# single_valve_board.net
KiCad netlist of a schematic drawn in EAGLE
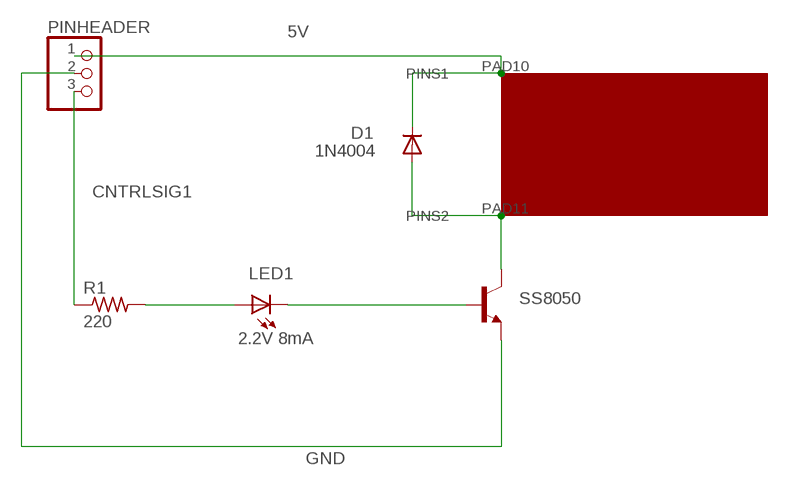
[diagram p0: schematic, sheet 1]

(export (version "E")
  (design (tool "Eeschema 10.0.6"))
  (components
    (comp (ref "D1")
      (value "1N4004")
      (footprint "eagle-import:DO41-10")
      (libsource (lib "eagle-import") (part "1N4004"))
    )
    (comp (ref "LED1")
      (value "2.2V 8mA")
      (footprint "eagle-import:LED5MM")
      (libsource (lib "eagle-import") (part "LED5MM"))
    )
    (comp (ref "PINHEADER")
      (value "PINHD-1X3")
      (footprint "eagle-import:1X03")
      (libsource (lib "eagle-import") (part "PINHD-1X3"))
    )
    (comp (ref "R1")
      (value "220")
      (footprint "eagle-import:0207_10")
      (libsource (lib "eagle-import") (part "R-US_0207/10"))
    )
    (comp (ref "SOLENOID1")
      (value "SOLENOID1")
      (footprint "eagle-import:VALVTEST2")
      (libsource (lib "eagle-import") (part "VALVE"))
    )
    (comp (ref "SS8050")
      (value "2N2222")
      (footprint "eagle-import:TO92-EBC-OVAL")
      (libsource (lib "eagle-import") (part "2N2222"))
    )
  )
  (nets
    (net (code "1") (name "/5V") (class "Default")
      (node (ref "D1") (pin "C") (pinfunction "C_C") (pintype "passive"))
      (node (ref "PINHEADER") (pin "1") (pinfunction "1_1") (pintype "passive"))
      (node (ref "SOLENOID1") (pin "PAD10") (pinfunction "PINS1_PAD10") (pintype "bidirectional"))
    )
    (net (code "2") (name "/CNTRLSIG1") (class "Default")
      (node (ref "PINHEADER") (pin "3") (pinfunction "3_3") (pintype "passive"))
      (node (ref "R1") (pin "1") (pinfunction "1_1") (pintype "passive"))
    )
    (net (code "3") (name "/GND") (class "Default")
      (node (ref "PINHEADER") (pin "2") (pinfunction "2_2") (pintype "passive"))
      (node (ref "SS8050") (pin "E") (pinfunction "E_E") (pintype "passive"))
    )
    (net (code "4") (name "Net-(LED1-C)") (class "Default")
      (node (ref "LED1") (pin "K") (pinfunction "C_K") (pintype "passive"))
      (node (ref "SS8050") (pin "B") (pinfunction "B_B") (pintype "passive"))
    )
    (net (code "5") (name "Net-(LED1-PadA)") (class "Default")
      (node (ref "LED1") (pin "A") (pinfunction "A_A") (pintype "passive"))
      (node (ref "R1") (pin "2") (pinfunction "2_2") (pintype "passive"))
    )
    (net (code "6") (name "Net-(SOLENOID1-PINS2)") (class "Default")
      (node (ref "D1") (pin "A") (pinfunction "A_A") (pintype "passive"))
      (node (ref "SOLENOID1") (pin "PAD11") (pinfunction "PINS2_PAD11") (pintype "bidirectional"))
      (node (ref "SS8050") (pin "C") (pinfunction "C_C") (pintype "passive"))
    )
  )
)
